# lipo.net
KiCad netlist of a schematic drawn in EAGLE
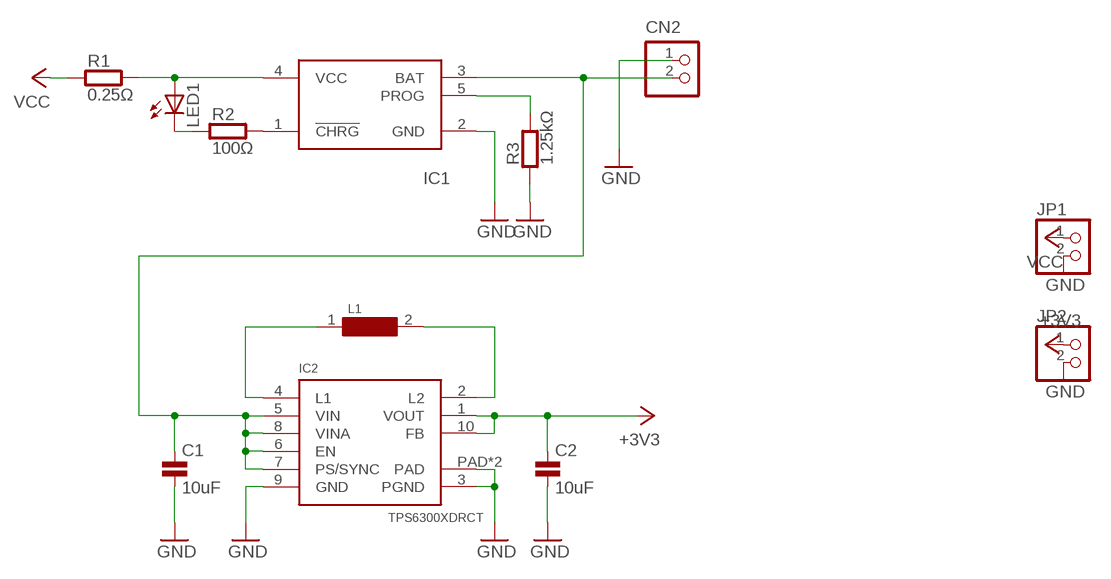
[diagram p0: schematic, sheet 1]

(export (version "E")
  (design (tool "Eeschema 10.0.6"))
  (components
    (comp (ref "C1")
      (value "10uF")
      (footprint "eagle-import:0603")
      (libsource (lib "eagle-import") (part "C0603"))
    )
    (comp (ref "C2")
      (value "10uF")
      (footprint "eagle-import:0603")
      (libsource (lib "eagle-import") (part "C0603"))
    )
    (comp (ref "CN2")
      (value "S2B-PH-K-S")
      (footprint "eagle-import:S2B-PH-K-S")
      (libsource (lib "eagle-import") (part "S2B-PH-K-S"))
    )
    (comp (ref "IC1")
      (value "LTC4054")
      (footprint "eagle-import:TSOT23-5")
      (libsource (lib "eagle-import") (part "LTC4054"))
    )
    (comp (ref "IC2")
      (value "TPS6300XDRCT")
      (footprint "eagle-import:S-PVSON-N10")
      (libsource (lib "eagle-import") (part "TPS6300XDRCT"))
    )
    (comp (ref "JP1")
      (value "PINHD-1X2")
      (footprint "eagle-import:1X02")
      (libsource (lib "eagle-import") (part "PINHD-1X2"))
    )
    (comp (ref "JP2")
      (value "PINHD-1X2")
      (footprint "eagle-import:1X02")
      (libsource (lib "eagle-import") (part "PINHD-1X2"))
    )
    (comp (ref "L1")
      (value "VLF4012ST")
      (footprint "eagle-import:VLF4012ST")
      (libsource (lib "eagle-import") (part "VLF4012ST"))
    )
    (comp (ref "LED1")
      (value "LEDSML0603")
      (footprint "eagle-import:SML0603")
      (libsource (lib "eagle-import") (part "LEDSML0603"))
    )
    (comp (ref "R1")
      (value "0.25Ω")
      (footprint "eagle-import:0603")
      (libsource (lib "eagle-import") (part "R0603"))
    )
    (comp (ref "R2")
      (value "100Ω")
      (footprint "eagle-import:0603")
      (libsource (lib "eagle-import") (part "R0603"))
    )
    (comp (ref "R3")
      (value "1.25kΩ")
      (footprint "eagle-import:0603")
      (libsource (lib "eagle-import") (part "R0603"))
    )
  )
  (nets
    (net (code "1") (name "+3V3") (class "Default")
      (node (ref "C2") (pin "1") (pinfunction "P$1_1") (pintype "passive"))
      (node (ref "IC2") (pin "1") (pinfunction "VOUT_1") (pintype "output"))
      (node (ref "IC2") (pin "10") (pinfunction "FB_10") (pintype "input"))
      (node (ref "JP2") (pin "1") (pinfunction "1_1") (pintype "passive"))
    )
    (net (code "2") (name "GND") (class "Default")
      (node (ref "C1") (pin "2") (pinfunction "P$2_2") (pintype "passive"))
      (node (ref "C2") (pin "2") (pinfunction "P$2_2") (pintype "passive"))
      (node (ref "CN2") (pin "1") (pinfunction "1_1") (pintype "passive"))
      (node (ref "IC1") (pin "2") (pinfunction "GND_2") (pintype "power_in"))
      (node (ref "IC2") (pin "3") (pinfunction "PGND_3") (pintype "power_in"))
      (node (ref "IC2") (pin "9") (pinfunction "GND_9") (pintype "power_in"))
      (node (ref "IC2") (pin "PAD") (pinfunction "PAD_PAD") (pintype "power_in"))
      (node (ref "IC2") (pin "PAD@1") (pinfunction "PAD_PAD@1") (pintype "power_in"))
      (node (ref "JP1") (pin "2") (pinfunction "2_2") (pintype "passive"))
      (node (ref "JP2") (pin "2") (pinfunction "2_2") (pintype "passive"))
      (node (ref "R3") (pin "1") (pinfunction "P$1_1") (pintype "passive"))
    )
    (net (code "3") (name "Net-(C1-P$1)") (class "Default")
      (node (ref "C1") (pin "1") (pinfunction "P$1_1") (pintype "passive"))
      (node (ref "CN2") (pin "2") (pinfunction "2_2") (pintype "passive"))
      (node (ref "IC1") (pin "3") (pinfunction "BAT_3") (pintype "power_in"))
      (node (ref "IC2") (pin "5") (pinfunction "VIN_5") (pintype "power_in"))
      (node (ref "IC2") (pin "6") (pinfunction "EN_6") (pintype "input"))
      (node (ref "IC2") (pin "7") (pinfunction "PS/SYNC_7") (pintype "input"))
      (node (ref "IC2") (pin "8") (pinfunction "VINA_8") (pintype "power_in"))
    )
    (net (code "4") (name "Net-(IC1-PROG)") (class "Default")
      (node (ref "IC1") (pin "5") (pinfunction "PROG_5") (pintype "passive"))
      (node (ref "R3") (pin "2") (pinfunction "P$2_2") (pintype "passive"))
    )
    (net (code "5") (name "Net-(IC1-VCC)") (class "Default")
      (node (ref "IC1") (pin "4") (pinfunction "VCC_4") (pintype "power_in"))
      (node (ref "LED1") (pin "A") (pinfunction "A_A") (pintype "passive"))
      (node (ref "R1") (pin "2") (pinfunction "P$2_2") (pintype "passive"))
    )
    (net (code "6") (name "Net-(IC1-~{CHRG})") (class "Default")
      (node (ref "IC1") (pin "1") (pinfunction "~{CHRG}_1") (pintype "output"))
      (node (ref "R2") (pin "2") (pinfunction "P$2_2") (pintype "passive"))
    )
    (net (code "7") (name "Net-(IC2-L1)") (class "Default")
      (node (ref "IC2") (pin "4") (pinfunction "L1_4") (pintype "bidirectional"))
      (node (ref "L1") (pin "1") (pinfunction "1_1") (pintype "passive"))
    )
    (net (code "8") (name "Net-(IC2-L2)") (class "Default")
      (node (ref "IC2") (pin "2") (pinfunction "L2_2") (pintype "bidirectional"))
      (node (ref "L1") (pin "2") (pinfunction "2_2") (pintype "passive"))
    )
    (net (code "9") (name "Net-(R2-P$1)") (class "Default")
      (node (ref "LED1") (pin "C") (pinfunction "C_C") (pintype "passive"))
      (node (ref "R2") (pin "1") (pinfunction "P$1_1") (pintype "passive"))
    )
    (net (code "10") (name "VCC") (class "Default")
      (node (ref "JP1") (pin "1") (pinfunction "1_1") (pintype "passive"))
      (node (ref "R1") (pin "1") (pinfunction "P$1_1") (pintype "passive"))
    )
  )
)
